# output-breakout.net
KiCad netlist of a schematic drawn in EAGLE
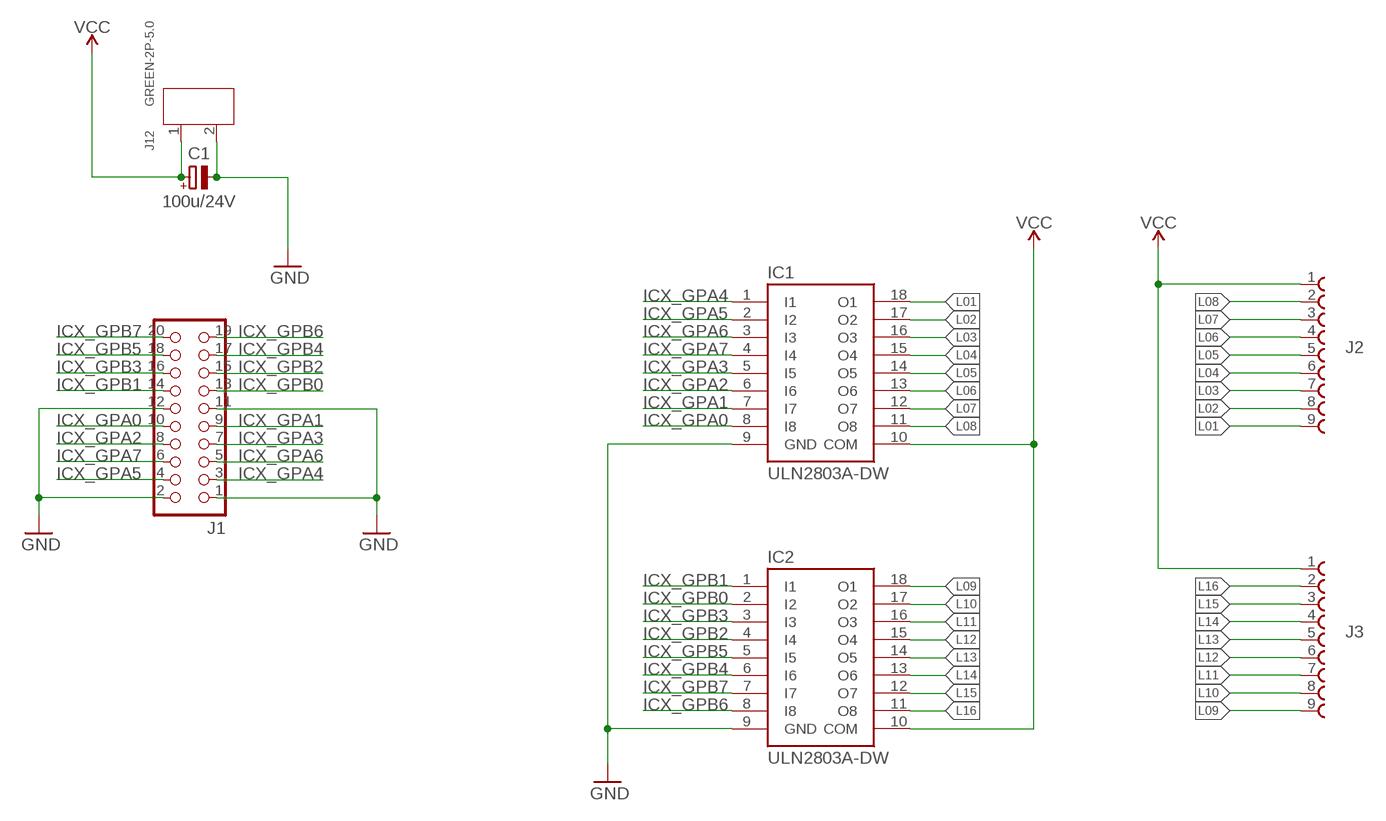
[diagram p0: schematic, sheet 1]

(export (version "E")
  (design (tool "Eeschema 10.0.6"))
  (components
    (comp (ref "C1")
      (value "100u/24V")
      (footprint "eagle-import:E3.5-8")
      (libsource (lib "eagle-import") (part "CAPACITOR_POL-E3.5-8"))
    )
    (comp (ref "IC1")
      (value "ULN2803A-DW")
      (footprint "eagle-import:SO18W")
      (libsource (lib "eagle-import") (part "ULN2803A-DW"))
    )
    (comp (ref "IC2")
      (value "ULN2803A-DW")
      (footprint "eagle-import:SO18W")
      (libsource (lib "eagle-import") (part "ULN2803A-DW"))
    )
    (comp (ref "J1")
      (value "CON_HEADER_2X10-SHROUDED")
      (footprint "eagle-import:PINSHRD_PTH_2X10")
      (libsource (lib "eagle-import") (part "CON_HEADER_2X10-SHROUDED"))
    )
    (comp (ref "J2")
      (value "69132211000_XX")
      (footprint "eagle-import:69132211000_XX")
      (libsource (lib "eagle-import") (part "69132211000_XX"))
    )
    (comp (ref "J3")
      (value "69132211000_XX")
      (footprint "eagle-import:69132211000_XX")
      (libsource (lib "eagle-import") (part "69132211000_XX"))
    )
    (comp (ref "J12")
      (value "GREEN-2P-5.0")
      (footprint "eagle-import:H2-5.0-10.5X8.0MM")
      (libsource (lib "eagle-import") (part "SCREW-TERMINAL-GREEN(2P-5.0)"))
    )
  )
  (nets
    (net (code "1") (name "/ICX_GPA0") (class "Default")
      (node (ref "IC1") (pin "8") (pinfunction "I8_8") (pintype "input"))
      (node (ref "J1") (pin "10") (pinfunction "10_10") (pintype "passive"))
    )
    (net (code "2") (name "/ICX_GPA1") (class "Default")
      (node (ref "IC1") (pin "7") (pinfunction "I7_7") (pintype "input"))
      (node (ref "J1") (pin "9") (pinfunction "9_9") (pintype "passive"))
    )
    (net (code "3") (name "/ICX_GPA2") (class "Default")
      (node (ref "IC1") (pin "6") (pinfunction "I6_6") (pintype "input"))
      (node (ref "J1") (pin "8") (pinfunction "8_8") (pintype "passive"))
    )
    (net (code "4") (name "/ICX_GPA3") (class "Default")
      (node (ref "IC1") (pin "5") (pinfunction "I5_5") (pintype "input"))
      (node (ref "J1") (pin "7") (pinfunction "7_7") (pintype "passive"))
    )
    (net (code "5") (name "/ICX_GPA4") (class "Default")
      (node (ref "IC1") (pin "1") (pinfunction "I1_1") (pintype "input"))
      (node (ref "J1") (pin "3") (pinfunction "3_3") (pintype "passive"))
    )
    (net (code "6") (name "/ICX_GPA5") (class "Default")
      (node (ref "IC1") (pin "2") (pinfunction "I2_2") (pintype "input"))
      (node (ref "J1") (pin "4") (pinfunction "4_4") (pintype "passive"))
    )
    (net (code "7") (name "/ICX_GPA6") (class "Default")
      (node (ref "IC1") (pin "3") (pinfunction "I3_3") (pintype "input"))
      (node (ref "J1") (pin "5") (pinfunction "5_5") (pintype "passive"))
    )
    (net (code "8") (name "/ICX_GPA7") (class "Default")
      (node (ref "IC1") (pin "4") (pinfunction "I4_4") (pintype "input"))
      (node (ref "J1") (pin "6") (pinfunction "6_6") (pintype "passive"))
    )
    (net (code "9") (name "/ICX_GPB0") (class "Default")
      (node (ref "IC2") (pin "2") (pinfunction "I2_2") (pintype "input"))
      (node (ref "J1") (pin "13") (pinfunction "13_13") (pintype "passive"))
    )
    (net (code "10") (name "/ICX_GPB1") (class "Default")
      (node (ref "IC2") (pin "1") (pinfunction "I1_1") (pintype "input"))
      (node (ref "J1") (pin "14") (pinfunction "14_14") (pintype "passive"))
    )
    (net (code "11") (name "/ICX_GPB2") (class "Default")
      (node (ref "IC2") (pin "4") (pinfunction "I4_4") (pintype "input"))
      (node (ref "J1") (pin "15") (pinfunction "15_15") (pintype "passive"))
    )
    (net (code "12") (name "/ICX_GPB3") (class "Default")
      (node (ref "IC2") (pin "3") (pinfunction "I3_3") (pintype "input"))
      (node (ref "J1") (pin "16") (pinfunction "16_16") (pintype "passive"))
    )
    (net (code "13") (name "/ICX_GPB4") (class "Default")
      (node (ref "IC2") (pin "6") (pinfunction "I6_6") (pintype "input"))
      (node (ref "J1") (pin "17") (pinfunction "17_17") (pintype "passive"))
    )
    (net (code "14") (name "/ICX_GPB5") (class "Default")
      (node (ref "IC2") (pin "5") (pinfunction "I5_5") (pintype "input"))
      (node (ref "J1") (pin "18") (pinfunction "18_18") (pintype "passive"))
    )
    (net (code "15") (name "/ICX_GPB6") (class "Default")
      (node (ref "IC2") (pin "8") (pinfunction "I8_8") (pintype "input"))
      (node (ref "J1") (pin "19") (pinfunction "19_19") (pintype "passive"))
    )
    (net (code "16") (name "/ICX_GPB7") (class "Default")
      (node (ref "IC2") (pin "7") (pinfunction "I7_7") (pintype "input"))
      (node (ref "J1") (pin "20") (pinfunction "20_20") (pintype "passive"))
    )
    (net (code "17") (name "GND") (class "Default")
      (node (ref "C1") (pin "-") (pinfunction "-_-") (pintype "passive"))
      (node (ref "IC1") (pin "9") (pinfunction "GND_9") (pintype "power_in"))
      (node (ref "IC2") (pin "9") (pinfunction "GND_9") (pintype "power_in"))
      (node (ref "J1") (pin "1") (pinfunction "1_1") (pintype "passive"))
      (node (ref "J1") (pin "11") (pinfunction "11_11") (pintype "passive"))
      (node (ref "J1") (pin "12") (pinfunction "12_12") (pintype "passive"))
      (node (ref "J1") (pin "2") (pinfunction "2_2") (pintype "passive"))
      (node (ref "J12") (pin "2") (pinfunction "2_2") (pintype "bidirectional"))
    )
    (net (code "18") (name "L01") (class "Default")
      (node (ref "IC1") (pin "18") (pinfunction "O1_18") (pintype "open_collector"))
      (node (ref "J2") (pin "9") (pinfunction "9_9") (pintype "passive"))
    )
    (net (code "19") (name "L02") (class "Default")
      (node (ref "IC1") (pin "17") (pinfunction "O2_17") (pintype "open_collector"))
      (node (ref "J2") (pin "8") (pinfunction "8_8") (pintype "passive"))
    )
    (net (code "20") (name "L03") (class "Default")
      (node (ref "IC1") (pin "16") (pinfunction "O3_16") (pintype "open_collector"))
      (node (ref "J2") (pin "7") (pinfunction "7_7") (pintype "passive"))
    )
    (net (code "21") (name "L04") (class "Default")
      (node (ref "IC1") (pin "15") (pinfunction "O4_15") (pintype "open_collector"))
      (node (ref "J2") (pin "6") (pinfunction "6_6") (pintype "passive"))
    )
    (net (code "22") (name "L05") (class "Default")
      (node (ref "IC1") (pin "14") (pinfunction "O5_14") (pintype "open_collector"))
      (node (ref "J2") (pin "5") (pinfunction "5_5") (pintype "passive"))
    )
    (net (code "23") (name "L06") (class "Default")
      (node (ref "IC1") (pin "13") (pinfunction "O6_13") (pintype "open_collector"))
      (node (ref "J2") (pin "4") (pinfunction "4_4") (pintype "passive"))
    )
    (net (code "24") (name "L07") (class "Default")
      (node (ref "IC1") (pin "12") (pinfunction "O7_12") (pintype "open_collector"))
      (node (ref "J2") (pin "3") (pinfunction "3_3") (pintype "passive"))
    )
    (net (code "25") (name "L08") (class "Default")
      (node (ref "IC1") (pin "11") (pinfunction "O8_11") (pintype "open_collector"))
      (node (ref "J2") (pin "2") (pinfunction "2_2") (pintype "passive"))
    )
    (net (code "26") (name "L09") (class "Default")
      (node (ref "IC2") (pin "18") (pinfunction "O1_18") (pintype "open_collector"))
      (node (ref "J3") (pin "9") (pinfunction "9_9") (pintype "passive"))
    )
    (net (code "27") (name "L10") (class "Default")
      (node (ref "IC2") (pin "17") (pinfunction "O2_17") (pintype "open_collector"))
      (node (ref "J3") (pin "8") (pinfunction "8_8") (pintype "passive"))
    )
    (net (code "28") (name "L11") (class "Default")
      (node (ref "IC2") (pin "16") (pinfunction "O3_16") (pintype "open_collector"))
      (node (ref "J3") (pin "7") (pinfunction "7_7") (pintype "passive"))
    )
    (net (code "29") (name "L12") (class "Default")
      (node (ref "IC2") (pin "15") (pinfunction "O4_15") (pintype "open_collector"))
      (node (ref "J3") (pin "6") (pinfunction "6_6") (pintype "passive"))
    )
    (net (code "30") (name "L13") (class "Default")
      (node (ref "IC2") (pin "14") (pinfunction "O5_14") (pintype "open_collector"))
      (node (ref "J3") (pin "5") (pinfunction "5_5") (pintype "passive"))
    )
    (net (code "31") (name "L14") (class "Default")
      (node (ref "IC2") (pin "13") (pinfunction "O6_13") (pintype "open_collector"))
      (node (ref "J3") (pin "4") (pinfunction "4_4") (pintype "passive"))
    )
    (net (code "32") (name "L15") (class "Default")
      (node (ref "IC2") (pin "12") (pinfunction "O7_12") (pintype "open_collector"))
      (node (ref "J3") (pin "3") (pinfunction "3_3") (pintype "passive"))
    )
    (net (code "33") (name "L16") (class "Default")
      (node (ref "IC2") (pin "11") (pinfunction "O8_11") (pintype "open_collector"))
      (node (ref "J3") (pin "2") (pinfunction "2_2") (pintype "passive"))
    )
    (net (code "34") (name "VCC") (class "Default")
      (node (ref "C1") (pin "+") (pinfunction "+_+") (pintype "passive"))
      (node (ref "IC1") (pin "10") (pinfunction "COM_10") (pintype "passive"))
      (node (ref "IC2") (pin "10") (pinfunction "COM_10") (pintype "passive"))
      (node (ref "J12") (pin "1") (pinfunction "1_1") (pintype "bidirectional"))
      (node (ref "J2") (pin "1") (pinfunction "1_1") (pintype "passive"))
      (node (ref "J3") (pin "1") (pinfunction "1_1") (pintype "passive"))
    )
  )
)
